# ihc_mon.net
KiCad netlist of a schematic drawn in EAGLE
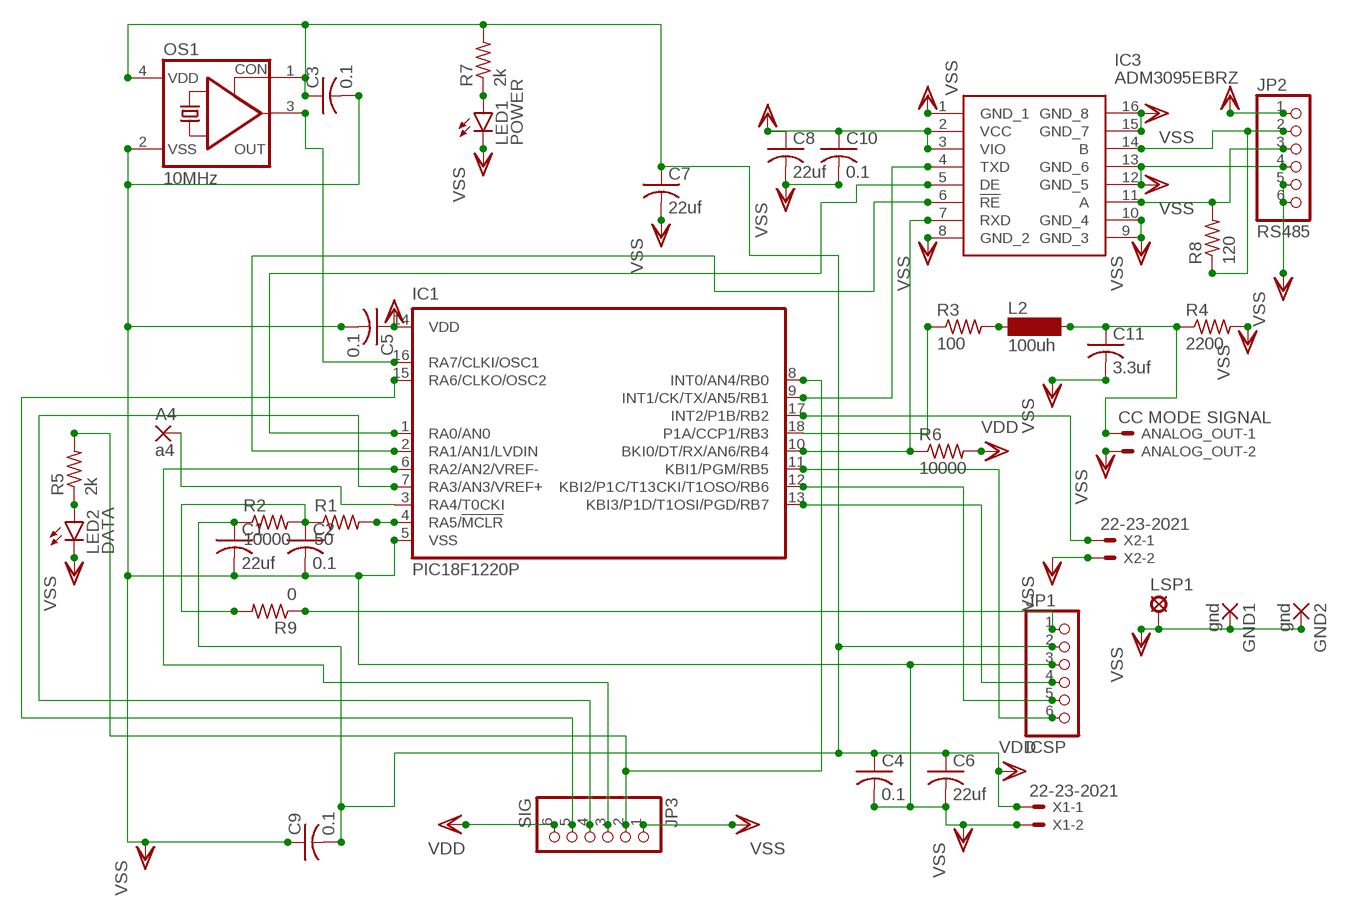
[diagram p0: schematic, sheet 1]

(export (version "E")
  (design (tool "Eeschema 10.0.6"))
  (components
    (comp (ref "A4")
      (value "a4")
      (footprint "eagle-import:SMD1,27-2,54")
      (libsource (lib "eagle-import") (part "SMD2"))
    )
    (comp (ref "ANALOG_OUT")
      (value "CC MODE SIGNAL")
      (footprint "eagle-import:22-23-2021")
      (fields (field (name "MF") "MOLEX") (field (name "MPN") "22-23-2021"))
      (libsource (lib "eagle-import") (part "22-23-2021"))
    )
    (comp (ref "C1")
      (value "22uf")
      (footprint "eagle-import:C0805")
      (libsource (lib "eagle-import") (part "C-USC0805"))
    )
    (comp (ref "C2")
      (value "0.1")
      (footprint "eagle-import:C0805")
      (libsource (lib "eagle-import") (part "C-USC0805"))
    )
    (comp (ref "C3")
      (value "0.1")
      (footprint "eagle-import:C0805")
      (libsource (lib "eagle-import") (part "C-USC0805"))
    )
    (comp (ref "C4")
      (value "0.1")
      (footprint "eagle-import:C0805")
      (libsource (lib "eagle-import") (part "C-USC0805"))
    )
    (comp (ref "C5")
      (value "0.1")
      (footprint "eagle-import:C0805")
      (libsource (lib "eagle-import") (part "C-USC0805"))
    )
    (comp (ref "C6")
      (value "22uf")
      (footprint "eagle-import:C0805")
      (libsource (lib "eagle-import") (part "C-USC0805"))
    )
    (comp (ref "C7")
      (value "22uf")
      (footprint "eagle-import:C0805")
      (libsource (lib "eagle-import") (part "C-USC0805"))
    )
    (comp (ref "C8")
      (value "22uf")
      (footprint "eagle-import:C0805")
      (libsource (lib "eagle-import") (part "C-USC0805"))
    )
    (comp (ref "C9")
      (value "0.1")
      (footprint "eagle-import:C0805")
      (libsource (lib "eagle-import") (part "C-USC0805"))
    )
    (comp (ref "C10")
      (value "0.1")
      (footprint "eagle-import:C0805")
      (libsource (lib "eagle-import") (part "C-USC0805"))
    )
    (comp (ref "C11")
      (value "3.3uf")
      (footprint "eagle-import:C0805")
      (libsource (lib "eagle-import") (part "C-USC0805"))
    )
    (comp (ref "GND1")
      (value "gnd")
      (footprint "eagle-import:3,81_1,4")
      (libsource (lib "eagle-import") (part "3,81/1,4"))
    )
    (comp (ref "GND2")
      (value "gnd")
      (footprint "eagle-import:SMD1,27-2,54")
      (libsource (lib "eagle-import") (part "SMD2"))
    )
    (comp (ref "IC1")
      (value "PIC18F1220P")
      (footprint "eagle-import:DIL18")
      (fields
        (field (name "MF") "MICROCHIP")
        (field (name "MPN") "PIC18F1220-I/P")
        (field (name "MPN_1") "PIC18F1320-I/P")
      )
      (libsource (lib "eagle-import") (part "PIC18F120P2"))
    )
    (comp (ref "IC3")
      (value "ADM3095EBRZ")
      (footprint "eagle-import:SOIC127P600X175-16N")
      (fields (field (name "MOUSER_PART_NUMBER") "584-ADM3095EBRZ"))
      (libsource (lib "eagle-import") (part "ADM3095EBRZ"))
    )
    (comp (ref "JP1")
      (value "ICSP")
      (footprint "eagle-import:1X06")
      (libsource (lib "eagle-import") (part "PINHD-1X6"))
    )
    (comp (ref "JP2")
      (value "RS485")
      (footprint "eagle-import:1X06")
      (libsource (lib "eagle-import") (part "PINHD-1X6"))
    )
    (comp (ref "JP3")
      (value "SIG")
      (footprint "eagle-import:1X06")
      (libsource (lib "eagle-import") (part "PINHD-1X6"))
    )
    (comp (ref "L2")
      (value "100uh")
      (footprint "eagle-import:SM-1206")
      (libsource (lib "eagle-import") (part "SM-1206"))
    )
    (comp (ref "LED1")
      (value "POWER")
      (footprint "eagle-import:CHIPLED_1206")
      (libsource (lib "eagle-import") (part "LEDCHIPLED_1206"))
    )
    (comp (ref "LED2")
      (value "DATA")
      (footprint "eagle-import:CHIPLED_1206")
      (libsource (lib "eagle-import") (part "LEDCHIPLED_1206"))
    )
    (comp (ref "LSP1")
      (value "SE14")
      (footprint "eagle-import:SE14")
      (libsource (lib "eagle-import") (part "SE14"))
    )
    (comp (ref "OS1")
      (value "10MHz")
      (footprint "eagle-import:7.2X5.2-4-PAD")
      (libsource (lib "eagle-import") (part "OSC-OE-CFPS-32"))
    )
    (comp (ref "R1")
      (value "50")
      (footprint "eagle-import:R0805")
      (libsource (lib "eagle-import") (part "R-US_R0805"))
    )
    (comp (ref "R2")
      (value "10000")
      (footprint "eagle-import:R0805")
      (libsource (lib "eagle-import") (part "R-US_R0805"))
    )
    (comp (ref "R3")
      (value "100")
      (footprint "eagle-import:R0805")
      (libsource (lib "eagle-import") (part "R-US_R0805"))
    )
    (comp (ref "R4")
      (value "2200")
      (footprint "eagle-import:R0805")
      (libsource (lib "eagle-import") (part "R-US_R0805"))
    )
    (comp (ref "R5")
      (value "2k")
      (footprint "eagle-import:R0805")
      (libsource (lib "eagle-import") (part "R-US_R0805"))
    )
    (comp (ref "R6")
      (value "10000")
      (footprint "eagle-import:R0805")
      (libsource (lib "eagle-import") (part "R-US_R0805"))
    )
    (comp (ref "R7")
      (value "2k")
      (footprint "eagle-import:R0805")
      (libsource (lib "eagle-import") (part "R-US_R0805"))
    )
    (comp (ref "R8")
      (value "120")
      (footprint "eagle-import:M1206")
      (libsource (lib "eagle-import") (part "R-US_M1206"))
    )
    (comp (ref "R9")
      (value "0")
      (footprint "eagle-import:R0805")
      (libsource (lib "eagle-import") (part "R-US_R0805"))
    )
    (comp (ref "X1")
      (value "22-23-2021")
      (footprint "eagle-import:22-23-2021")
      (fields (field (name "MF") "MOLEX"))
      (libsource (lib "eagle-import") (part "22-23-2021"))
    )
    (comp (ref "X2")
      (value "22-23-2021")
      (footprint "eagle-import:22-23-2021")
      (fields (field (name "MF") "MOLEX"))
      (libsource (lib "eagle-import") (part "22-23-2021"))
    )
  )
  (nets
    (net (code "1") (name "Net-(A4-P)") (class "Default")
      (node (ref "A4") (pin "1") (pinfunction "P_1") (pintype "passive"))
      (node (ref "IC1") (pin "3") (pinfunction "RA4/T0CKI_3") (pintype "bidirectional"))
    )
    (net (code "2") (name "Net-(ANALOG_OUTA-S)") (class "Default")
      (node (ref "ANALOG_OUT") (pin "1") (pinfunction "S_1") (pintype "passive"))
      (node (ref "C11") (pin "1") (pinfunction "1_1") (pintype "passive"))
      (node (ref "L2") (pin "2") (pinfunction "2_2") (pintype "passive"))
      (node (ref "R4") (pin "1") (pinfunction "1_1") (pintype "passive"))
    )
    (net (code "3") (name "Net-(C2-Pad1)") (class "Default")
      (node (ref "C2") (pin "1") (pinfunction "1_1") (pintype "passive"))
      (node (ref "R1") (pin "1") (pinfunction "1_1") (pintype "passive"))
      (node (ref "R2") (pin "2") (pinfunction "2_2") (pintype "passive"))
      (node (ref "R9") (pin "2") (pinfunction "2_2") (pintype "passive"))
    )
    (net (code "4") (name "Net-(IC1-BKI0{slash}DT{slash}RX{slash}AN6{slash}RB4)") (class "Default")
      (node (ref "IC1") (pin "10") (pinfunction "BKI0/DT/RX/AN6/RB4_10") (pintype "bidirectional"))
      (node (ref "IC3") (pin "7") (pinfunction "RXD_7") (pintype "output"))
      (node (ref "R6") (pin "1") (pinfunction "1_1") (pintype "passive"))
    )
    (net (code "5") (name "Net-(IC1-INT0{slash}AN4{slash}RB0)") (class "Default")
      (node (ref "IC1") (pin "8") (pinfunction "INT0/AN4/RB0_8") (pintype "bidirectional"))
      (node (ref "JP3") (pin "2") (pinfunction "2_2") (pintype "passive"))
      (node (ref "R5") (pin "2") (pinfunction "2_2") (pintype "passive"))
    )
    (net (code "6") (name "Net-(IC1-INT1{slash}CK{slash}TX{slash}AN5{slash}RB1)") (class "Default")
      (node (ref "IC1") (pin "9") (pinfunction "INT1/CK/TX/AN5/RB1_9") (pintype "bidirectional"))
      (node (ref "IC3") (pin "4") (pinfunction "TXD_4") (pintype "input"))
    )
    (net (code "7") (name "Net-(IC1-INT2{slash}P1B{slash}RB2)") (class "Default")
      (node (ref "IC1") (pin "17") (pinfunction "INT2/P1B/RB2_17") (pintype "bidirectional"))
      (node (ref "X2") (pin "1") (pinfunction "S_1") (pintype "passive"))
    )
    (net (code "8") (name "Net-(IC1-KBI1{slash}PGM{slash}RB5)") (class "Default")
      (node (ref "IC1") (pin "11") (pinfunction "KBI1/PGM/RB5_11") (pintype "bidirectional"))
      (node (ref "JP1") (pin "6") (pinfunction "6_6") (pintype "passive"))
    )
    (net (code "9") (name "Net-(IC1-KBI2{slash}P1C{slash}T13CKI{slash}T1OSO{slash}RB6)") (class "Default")
      (node (ref "IC1") (pin "12") (pinfunction "KBI2/P1C/T13CKI/T1OSO/RB6_12") (pintype "bidirectional"))
      (node (ref "JP1") (pin "5") (pinfunction "5_5") (pintype "passive"))
    )
    (net (code "10") (name "Net-(IC1-KBI3{slash}P1D{slash}T1OSI{slash}PGD{slash}RB7)") (class "Default")
      (node (ref "IC1") (pin "13") (pinfunction "KBI3/P1D/T1OSI/PGD/RB7_13") (pintype "bidirectional"))
      (node (ref "JP1") (pin "4") (pinfunction "4_4") (pintype "passive"))
    )
    (net (code "11") (name "Net-(IC1-P1A{slash}CCP1{slash}RB3)") (class "Default")
      (node (ref "IC1") (pin "18") (pinfunction "P1A/CCP1/RB3_18") (pintype "bidirectional"))
      (node (ref "R3") (pin "1") (pinfunction "1_1") (pintype "passive"))
    )
    (net (code "12") (name "Net-(IC1-RA0{slash}AN0)") (class "Default")
      (node (ref "IC1") (pin "1") (pinfunction "RA0/AN0_1") (pintype "bidirectional"))
      (node (ref "IC3") (pin "5") (pinfunction "DE_5") (pintype "input"))
    )
    (net (code "13") (name "Net-(IC1-RA1{slash}AN1{slash}LVDIN)") (class "Default")
      (node (ref "IC1") (pin "2") (pinfunction "RA1/AN1/LVDIN_2") (pintype "bidirectional"))
      (node (ref "IC3") (pin "6") (pinfunction "~{RE}_6") (pintype "input"))
    )
    (net (code "14") (name "Net-(IC1-RA2{slash}AN2{slash}VREF-)") (class "Default")
      (node (ref "IC1") (pin "6") (pinfunction "RA2/AN2/VREF-_6") (pintype "bidirectional"))
      (node (ref "JP3") (pin "3") (pinfunction "3_3") (pintype "passive"))
    )
    (net (code "15") (name "Net-(IC1-RA3{slash}AN3{slash}VREF+)") (class "Default")
      (node (ref "IC1") (pin "7") (pinfunction "RA3/AN3/VREF+_7") (pintype "bidirectional"))
      (node (ref "JP3") (pin "4") (pinfunction "4_4") (pintype "passive"))
    )
    (net (code "16") (name "Net-(IC1-RA5{slash}~{MCLR})") (class "Default")
      (node (ref "IC1") (pin "4") (pinfunction "RA5/~{MCLR}_4") (pintype "input"))
      (node (ref "R1") (pin "2") (pinfunction "2_2") (pintype "passive"))
    )
    (net (code "17") (name "Net-(IC1-RA6{slash}CLKO{slash}OSC2)") (class "Default")
      (node (ref "IC1") (pin "15") (pinfunction "RA6/CLKO/OSC2_15") (pintype "bidirectional"))
      (node (ref "JP3") (pin "5") (pinfunction "5_5") (pintype "passive"))
    )
    (net (code "18") (name "Net-(IC1-RA7{slash}CLKI{slash}OSC1)") (class "Default")
      (node (ref "IC1") (pin "16") (pinfunction "RA7/CLKI/OSC1_16") (pintype "bidirectional"))
      (node (ref "OS1") (pin "3") (pinfunction "OUT_3") (pintype "output"))
    )
    (net (code "19") (name "Net-(IC3-A)") (class "Default")
      (node (ref "IC3") (pin "11") (pinfunction "A_11") (pintype "bidirectional"))
      (node (ref "JP2") (pin "3") (pinfunction "3_3") (pintype "passive"))
      (node (ref "R8") (pin "2") (pinfunction "2_2") (pintype "passive"))
    )
    (net (code "20") (name "Net-(IC3-B)") (class "Default")
      (node (ref "IC3") (pin "14") (pinfunction "B_14") (pintype "bidirectional"))
      (node (ref "JP2") (pin "2") (pinfunction "2_2") (pintype "passive"))
      (node (ref "R8") (pin "1") (pinfunction "1_1") (pintype "passive"))
    )
    (net (code "21") (name "Net-(JP1-Pad1)") (class "Default")
      (node (ref "JP1") (pin "1") (pinfunction "1_1") (pintype "passive"))
      (node (ref "R9") (pin "1") (pinfunction "1_1") (pintype "passive"))
    )
    (net (code "22") (name "Net-(L2-Pad1)") (class "Default")
      (node (ref "L2") (pin "1") (pinfunction "1_1") (pintype "passive"))
      (node (ref "R3") (pin "2") (pinfunction "2_2") (pintype "passive"))
    )
    (net (code "23") (name "Net-(LED1-PadA)") (class "Default")
      (node (ref "LED1") (pin "A") (pinfunction "A_A") (pintype "passive"))
      (node (ref "R7") (pin "1") (pinfunction "1_1") (pintype "passive"))
    )
    (net (code "24") (name "Net-(LED2-PadA)") (class "Default")
      (node (ref "LED2") (pin "A") (pinfunction "A_A") (pintype "passive"))
      (node (ref "R5") (pin "1") (pinfunction "1_1") (pintype "passive"))
    )
    (net (code "25") (name "VDD") (class "Default")
      (node (ref "C1") (pin "1") (pinfunction "1_1") (pintype "passive"))
      (node (ref "C10") (pin "1") (pinfunction "1_1") (pintype "passive"))
      (node (ref "C3") (pin "1") (pinfunction "1_1") (pintype "passive"))
      (node (ref "C4") (pin "1") (pinfunction "1_1") (pintype "passive"))
      (node (ref "C5") (pin "1") (pinfunction "1_1") (pintype "passive"))
      (node (ref "C6") (pin "1") (pinfunction "1_1") (pintype "passive"))
      (node (ref "C7") (pin "1") (pinfunction "1_1") (pintype "passive"))
      (node (ref "C8") (pin "1") (pinfunction "1_1") (pintype "passive"))
      (node (ref "C9") (pin "2") (pinfunction "2_2") (pintype "passive"))
      (node (ref "IC1") (pin "14") (pinfunction "VDD_14") (pintype "power_in"))
      (node (ref "IC3") (pin "2") (pinfunction "VCC_2") (pintype "power_in"))
      (node (ref "IC3") (pin "3") (pinfunction "VIO_3") (pintype "power_in"))
      (node (ref "JP1") (pin "2") (pinfunction "2_2") (pintype "passive"))
      (node (ref "JP2") (pin "1") (pinfunction "1_1") (pintype "passive"))
      (node (ref "JP3") (pin "6") (pinfunction "6_6") (pintype "passive"))
      (node (ref "OS1") (pin "1") (pinfunction "CON_1") (pintype "input"))
      (node (ref "OS1") (pin "4") (pinfunction "VDD_4") (pintype "power_in"))
      (node (ref "R2") (pin "1") (pinfunction "1_1") (pintype "passive"))
      (node (ref "R6") (pin "2") (pinfunction "2_2") (pintype "passive"))
      (node (ref "R7") (pin "2") (pinfunction "2_2") (pintype "passive"))
      (node (ref "X1") (pin "1") (pinfunction "S_1") (pintype "passive"))
    )
    (net (code "26") (name "VSS") (class "Default")
      (node (ref "ANALOG_OUT") (pin "2") (pinfunction "S_2") (pintype "passive"))
      (node (ref "C1") (pin "2") (pinfunction "2_2") (pintype "passive"))
      (node (ref "C10") (pin "2") (pinfunction "2_2") (pintype "passive"))
      (node (ref "C11") (pin "2") (pinfunction "2_2") (pintype "passive"))
      (node (ref "C2") (pin "2") (pinfunction "2_2") (pintype "passive"))
      (node (ref "C3") (pin "2") (pinfunction "2_2") (pintype "passive"))
      (node (ref "C4") (pin "2") (pinfunction "2_2") (pintype "passive"))
      (node (ref "C5") (pin "2") (pinfunction "2_2") (pintype "passive"))
      (node (ref "C6") (pin "2") (pinfunction "2_2") (pintype "passive"))
      (node (ref "C7") (pin "2") (pinfunction "2_2") (pintype "passive"))
      (node (ref "C8") (pin "2") (pinfunction "2_2") (pintype "passive"))
      (node (ref "C9") (pin "1") (pinfunction "1_1") (pintype "passive"))
      (node (ref "GND1") (pin "1") (pinfunction "P_1") (pintype "passive"))
      (node (ref "GND2") (pin "1") (pinfunction "P_1") (pintype "passive"))
      (node (ref "IC1") (pin "5") (pinfunction "VSS_5") (pintype "power_in"))
      (node (ref "IC3") (pin "1") (pinfunction "GND_1_1") (pintype "power_in"))
      (node (ref "IC3") (pin "10") (pinfunction "GND_4_10") (pintype "power_in"))
      (node (ref "IC3") (pin "12") (pinfunction "GND_5_12") (pintype "power_in"))
      (node (ref "IC3") (pin "13") (pinfunction "GND_6_13") (pintype "power_in"))
      (node (ref "IC3") (pin "15") (pinfunction "GND_7_15") (pintype "power_in"))
      (node (ref "IC3") (pin "16") (pinfunction "GND_8_16") (pintype "power_in"))
      (node (ref "IC3") (pin "8") (pinfunction "GND_2_8") (pintype "power_in"))
      (node (ref "IC3") (pin "9") (pinfunction "GND_3_9") (pintype "power_in"))
      (node (ref "JP1") (pin "3") (pinfunction "3_3") (pintype "passive"))
      (node (ref "JP2") (pin "4") (pinfunction "4_4") (pintype "passive"))
      (node (ref "JP2") (pin "5") (pinfunction "5_5") (pintype "passive"))
      (node (ref "JP2") (pin "6") (pinfunction "6_6") (pintype "passive"))
      (node (ref "JP3") (pin "1") (pinfunction "1_1") (pintype "passive"))
      (node (ref "LED1") (pin "C") (pinfunction "C_C") (pintype "passive"))
      (node (ref "LED2") (pin "C") (pinfunction "C_C") (pintype "passive"))
      (node (ref "LSP1") (pin "MP") (pinfunction "MP_MP") (pintype "passive"))
      (node (ref "OS1") (pin "2") (pinfunction "VSS_2") (pintype "power_in"))
      (node (ref "R4") (pin "2") (pinfunction "2_2") (pintype "passive"))
      (node (ref "X1") (pin "2") (pinfunction "S_2") (pintype "passive"))
      (node (ref "X2") (pin "2") (pinfunction "S_2") (pintype "passive"))
    )
  )
)
